# youuuuuuh.net
KiCad netlist of a schematic drawn in EAGLE
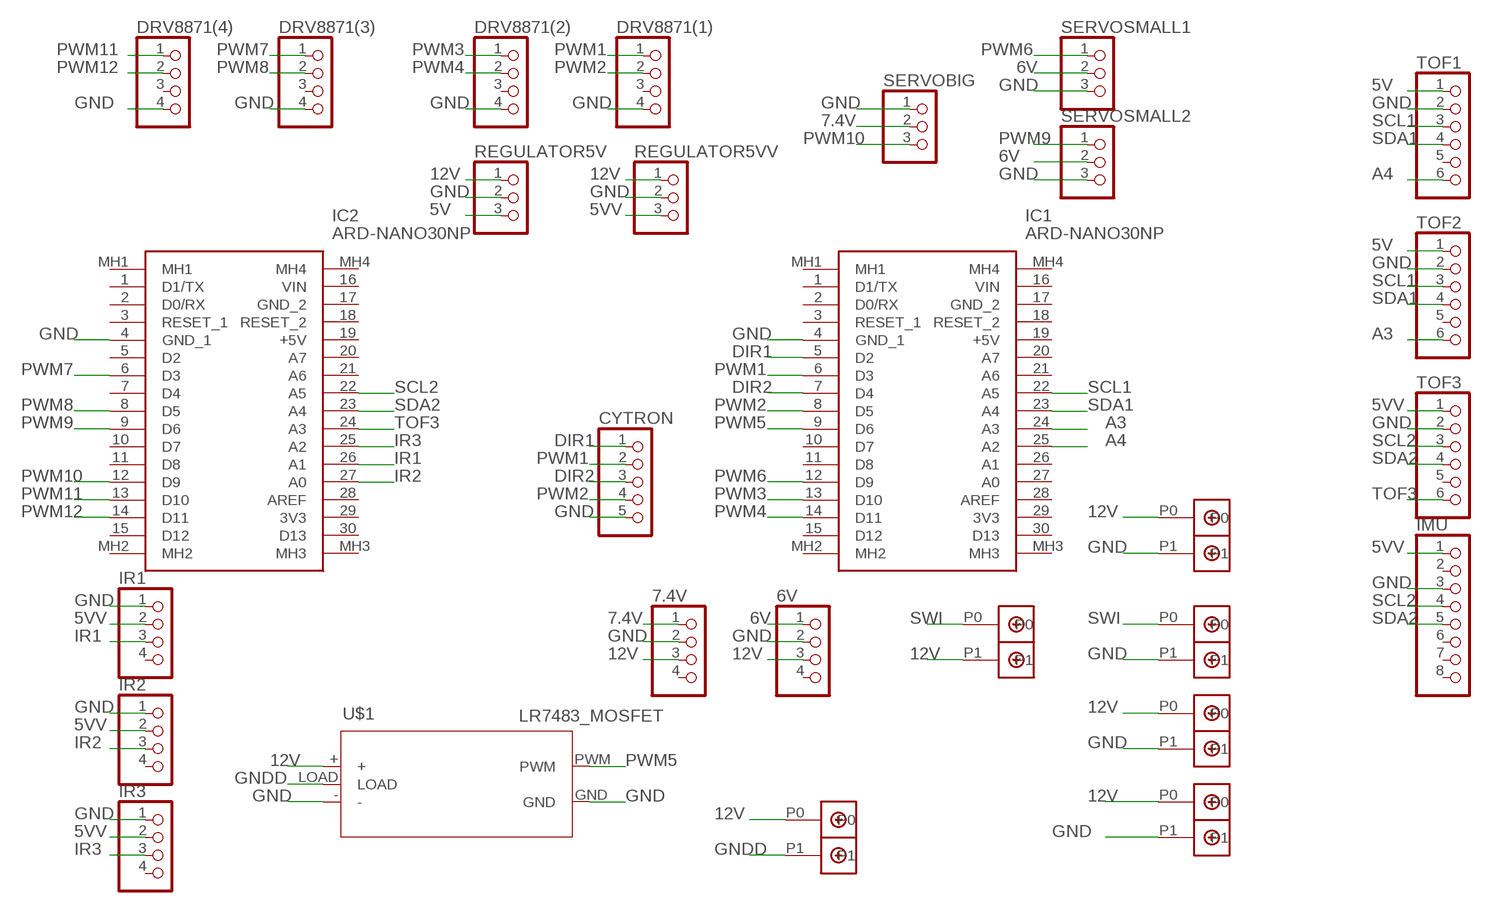
[diagram p0: schematic, sheet 1]

(export (version "E")
  (design (tool "Eeschema 10.0.6"))
  (components
    (comp (ref "6V")
      (value "PINHD-1X4")
      (footprint "eagle-import:1X04")
      (libsource (lib "eagle-import") (part "pinhead_325_PINHD-1X4"))
    )
    (comp (ref "7.4V")
      (value "PINHD-1X4")
      (footprint "eagle-import:1X04")
      (libsource (lib "eagle-import") (part "pinhead_325_PINHD-1X4"))
    )
    (comp (ref "BATERY")
      (value "DBCONN-1X2")
      (footprint "eagle-import:DBCONN-1X2")
      (libsource (lib "eagle-import") (part "DBCONN-1X2"))
    )
    (comp (ref "BUCKSERVO")
      (value "DBCONN-1X2")
      (footprint "eagle-import:DBCONN-1X2")
      (libsource (lib "eagle-import") (part "DBCONN-1X2"))
    )
    (comp (ref "CYTRON")
      (value "PINHD-1X5")
      (footprint "eagle-import:1X05")
      (libsource (lib "eagle-import") (part "PINHD-1X5"))
    )
    (comp (ref "CYTRONPOWER")
      (value "DBCONN-1X2")
      (footprint "eagle-import:DBCONN-1X2")
      (libsource (lib "eagle-import") (part "DBCONN-1X2"))
    )
    (comp (ref "DRV8871(1)")
      (value "PINHD-1X4")
      (footprint "eagle-import:1X04")
      (libsource (lib "eagle-import") (part "pinhead_325_PINHD-1X4"))
    )
    (comp (ref "DRV8871(2)")
      (value "PINHD-1X4")
      (footprint "eagle-import:1X04")
      (libsource (lib "eagle-import") (part "pinhead_325_PINHD-1X4"))
    )
    (comp (ref "DRV8871(3)")
      (value "PINHD-1X4")
      (footprint "eagle-import:1X04")
      (libsource (lib "eagle-import") (part "pinhead_325_PINHD-1X4"))
    )
    (comp (ref "DRV8871(4)")
      (value "PINHD-1X4")
      (footprint "eagle-import:1X04")
      (libsource (lib "eagle-import") (part "pinhead_325_PINHD-1X4"))
    )
    (comp (ref "IC1")
      (value "ARD-NANO30NP")
      (footprint "eagle-import:ARDNANO30NP")
      (fields (field (name "MOUSER_PART_NUMBER") "992-ARD-NANO30NP"))
      (libsource (lib "eagle-import") (part "ARD-NANO30NP"))
    )
    (comp (ref "IC2")
      (value "ARD-NANO30NP")
      (footprint "eagle-import:ARDNANO30NP")
      (fields (field (name "MOUSER_PART_NUMBER") "992-ARD-NANO30NP"))
      (libsource (lib "eagle-import") (part "ARD-NANO30NP"))
    )
    (comp (ref "IMU")
      (value "PINHD-1X8")
      (footprint "eagle-import:1X08")
      (libsource (lib "eagle-import") (part "PINHD-1X8"))
    )
    (comp (ref "IR1")
      (value "PINHD-1X4")
      (footprint "eagle-import:1X04")
      (libsource (lib "eagle-import") (part "PINHD-1X4"))
    )
    (comp (ref "IR2")
      (value "PINHD-1X4")
      (footprint "eagle-import:1X04")
      (libsource (lib "eagle-import") (part "PINHD-1X4"))
    )
    (comp (ref "IR3")
      (value "PINHD-1X4")
      (footprint "eagle-import:1X04")
      (libsource (lib "eagle-import") (part "PINHD-1X4"))
    )
    (comp (ref "LEDS1")
      (value "DBCONN-1X2")
      (footprint "eagle-import:DBCONN-1X2")
      (libsource (lib "eagle-import") (part "DBCONN-1X2"))
    )
    (comp (ref "LEDS2")
      (value "DBCONN-1X2")
      (footprint "eagle-import:DBCONN-1X2")
      (libsource (lib "eagle-import") (part "DBCONN-1X2"))
    )
    (comp (ref "LEDS3")
      (value "DBCONN-1X2")
      (footprint "eagle-import:DBCONN-1X2")
      (libsource (lib "eagle-import") (part "DBCONN-1X2"))
    )
    (comp (ref "REGULATOR5V")
      (value "PINHD-1X3")
      (footprint "eagle-import:1X03")
      (libsource (lib "eagle-import") (part "pinhead_325_PINHD-1X3"))
    )
    (comp (ref "REGULATOR5VV")
      (value "PINHD-1X3")
      (footprint "eagle-import:1X03")
      (libsource (lib "eagle-import") (part "PINHD-1X3"))
    )
    (comp (ref "SERVOBIG")
      (value "PINHD-1X3")
      (footprint "eagle-import:1X03")
      (libsource (lib "eagle-import") (part "pinhead_325_PINHD-1X3"))
    )
    (comp (ref "SERVOSMALL1")
      (value "PINHD-1X3")
      (footprint "eagle-import:1X03")
      (libsource (lib "eagle-import") (part "pinhead_325_PINHD-1X3"))
    )
    (comp (ref "SERVOSMALL2")
      (value "PINHD-1X3")
      (footprint "eagle-import:1X03")
      (libsource (lib "eagle-import") (part "pinhead_325_PINHD-1X3"))
    )
    (comp (ref "TOF1")
      (value "PINHD-1X6")
      (footprint "eagle-import:1X06")
      (libsource (lib "eagle-import") (part "PINHD-1X6"))
    )
    (comp (ref "TOF2")
      (value "PINHD-1X6")
      (footprint "eagle-import:1X06")
      (libsource (lib "eagle-import") (part "PINHD-1X6"))
    )
    (comp (ref "TOF3")
      (value "PINHD-1X6")
      (footprint "eagle-import:1X06")
      (libsource (lib "eagle-import") (part "PINHD-1X6"))
    )
    (comp (ref "U$1")
      (value "LR7483_MOSFET")
      (footprint "eagle-import:LR7483_MOSFET")
      (libsource (lib "eagle-import") (part "LR7483_MOSFET"))
    )
  )
  (nets
    (net (code "1") (name "/5V") (class "Default")
      (node (ref "REGULATOR5V") (pin "3") (pinfunction "3_3") (pintype "passive"))
      (node (ref "TOF1") (pin "1") (pinfunction "1_1") (pintype "passive"))
      (node (ref "TOF2") (pin "1") (pinfunction "1_1") (pintype "passive"))
    )
    (net (code "2") (name "/5VV") (class "Default")
      (node (ref "IMU") (pin "1") (pinfunction "1_1") (pintype "passive"))
      (node (ref "IR1") (pin "2") (pinfunction "2_2") (pintype "passive"))
      (node (ref "IR2") (pin "2") (pinfunction "2_2") (pintype "passive"))
      (node (ref "IR3") (pin "2") (pinfunction "2_2") (pintype "passive"))
      (node (ref "REGULATOR5VV") (pin "3") (pinfunction "3_3") (pintype "passive"))
      (node (ref "TOF3") (pin "1") (pinfunction "1_1") (pintype "passive"))
    )
    (net (code "3") (name "/6V") (class "Default")
      (node (ref "6V") (pin "1") (pinfunction "1_1") (pintype "passive"))
      (node (ref "SERVOSMALL1") (pin "2") (pinfunction "2_2") (pintype "passive"))
      (node (ref "SERVOSMALL2") (pin "2") (pinfunction "2_2") (pintype "passive"))
    )
    (net (code "4") (name "/7.4V") (class "Default")
      (node (ref "7.4V") (pin "1") (pinfunction "1_1") (pintype "passive"))
      (node (ref "SERVOBIG") (pin "2") (pinfunction "2_2") (pintype "passive"))
    )
    (net (code "5") (name "/12V") (class "Default")
      (node (ref "6V") (pin "3") (pinfunction "3_3") (pintype "passive"))
      (node (ref "7.4V") (pin "3") (pinfunction "3_3") (pintype "passive"))
      (node (ref "BUCKSERVO") (pin "P0") (pinfunction "P0_P0") (pintype "bidirectional"))
      (node (ref "CYTRONPOWER") (pin "P0") (pinfunction "P0_P0") (pintype "bidirectional"))
      (node (ref "LEDS1") (pin "P1") (pinfunction "P1_P1") (pintype "bidirectional"))
      (node (ref "LEDS2") (pin "P0") (pinfunction "P0_P0") (pintype "bidirectional"))
      (node (ref "LEDS3") (pin "P0") (pinfunction "P0_P0") (pintype "bidirectional"))
      (node (ref "REGULATOR5V") (pin "1") (pinfunction "1_1") (pintype "passive"))
      (node (ref "REGULATOR5VV") (pin "1") (pinfunction "1_1") (pintype "passive"))
      (node (ref "U$1") (pin "+") (pinfunction "+_+") (pintype "bidirectional"))
    )
    (net (code "6") (name "/A3") (class "Default")
      (node (ref "IC1") (pin "24") (pinfunction "A3_24") (pintype "bidirectional"))
      (node (ref "TOF2") (pin "6") (pinfunction "6_6") (pintype "passive"))
    )
    (net (code "7") (name "/A4") (class "Default")
      (node (ref "IC1") (pin "25") (pinfunction "A2_25") (pintype "bidirectional"))
      (node (ref "TOF1") (pin "6") (pinfunction "6_6") (pintype "passive"))
    )
    (net (code "8") (name "/DIR1") (class "Default")
      (node (ref "CYTRON") (pin "1") (pinfunction "1_1") (pintype "passive"))
      (node (ref "IC1") (pin "5") (pinfunction "D2_5") (pintype "bidirectional"))
    )
    (net (code "9") (name "/DIR2") (class "Default")
      (node (ref "CYTRON") (pin "3") (pinfunction "3_3") (pintype "passive"))
      (node (ref "IC1") (pin "7") (pinfunction "D4_7") (pintype "bidirectional"))
    )
    (net (code "10") (name "/GND") (class "Default")
      (node (ref "6V") (pin "2") (pinfunction "2_2") (pintype "passive"))
      (node (ref "7.4V") (pin "2") (pinfunction "2_2") (pintype "passive"))
      (node (ref "BATERY") (pin "P1") (pinfunction "P1_P1") (pintype "bidirectional"))
      (node (ref "BUCKSERVO") (pin "P1") (pinfunction "P1_P1") (pintype "bidirectional"))
      (node (ref "CYTRON") (pin "5") (pinfunction "5_5") (pintype "passive"))
      (node (ref "CYTRONPOWER") (pin "P1") (pinfunction "P1_P1") (pintype "bidirectional"))
      (node (ref "DRV8871(1)") (pin "4") (pinfunction "4_4") (pintype "passive"))
      (node (ref "DRV8871(2)") (pin "4") (pinfunction "4_4") (pintype "passive"))
      (node (ref "DRV8871(3)") (pin "4") (pinfunction "4_4") (pintype "passive"))
      (node (ref "DRV8871(4)") (pin "4") (pinfunction "4_4") (pintype "passive"))
      (node (ref "IC1") (pin "4") (pinfunction "GND_1_4") (pintype "bidirectional"))
      (node (ref "IC2") (pin "4") (pinfunction "GND_1_4") (pintype "bidirectional"))
      (node (ref "IMU") (pin "3") (pinfunction "3_3") (pintype "passive"))
      (node (ref "IR1") (pin "1") (pinfunction "1_1") (pintype "passive"))
      (node (ref "IR2") (pin "1") (pinfunction "1_1") (pintype "passive"))
      (node (ref "IR3") (pin "1") (pinfunction "1_1") (pintype "passive"))
      (node (ref "LEDS2") (pin "P1") (pinfunction "P1_P1") (pintype "bidirectional"))
      (node (ref "REGULATOR5V") (pin "2") (pinfunction "2_2") (pintype "passive"))
      (node (ref "REGULATOR5VV") (pin "2") (pinfunction "2_2") (pintype "passive"))
      (node (ref "SERVOBIG") (pin "1") (pinfunction "1_1") (pintype "passive"))
      (node (ref "SERVOSMALL1") (pin "3") (pinfunction "3_3") (pintype "passive"))
      (node (ref "SERVOSMALL2") (pin "3") (pinfunction "3_3") (pintype "passive"))
      (node (ref "TOF1") (pin "2") (pinfunction "2_2") (pintype "passive"))
      (node (ref "TOF2") (pin "2") (pinfunction "2_2") (pintype "passive"))
      (node (ref "TOF3") (pin "2") (pinfunction "2_2") (pintype "passive"))
      (node (ref "U$1") (pin "-") (pinfunction "-_-") (pintype "bidirectional"))
      (node (ref "U$1") (pin "GND") (pinfunction "GND_GND") (pintype "bidirectional"))
    )
    (net (code "11") (name "/GNDD") (class "Default")
      (node (ref "LEDS3") (pin "P1") (pinfunction "P1_P1") (pintype "bidirectional"))
      (node (ref "U$1") (pin "LOAD") (pinfunction "LOAD_LOAD") (pintype "bidirectional"))
    )
    (net (code "12") (name "/IR1") (class "Default")
      (node (ref "IC2") (pin "26") (pinfunction "A1_26") (pintype "bidirectional"))
      (node (ref "IR1") (pin "3") (pinfunction "3_3") (pintype "passive"))
    )
    (net (code "13") (name "/IR2") (class "Default")
      (node (ref "IC2") (pin "27") (pinfunction "A0_27") (pintype "bidirectional"))
      (node (ref "IR2") (pin "3") (pinfunction "3_3") (pintype "passive"))
    )
    (net (code "14") (name "/IR3") (class "Default")
      (node (ref "IC2") (pin "25") (pinfunction "A2_25") (pintype "bidirectional"))
      (node (ref "IR3") (pin "3") (pinfunction "3_3") (pintype "passive"))
    )
    (net (code "15") (name "/PWM1") (class "Default")
      (node (ref "CYTRON") (pin "2") (pinfunction "2_2") (pintype "passive"))
      (node (ref "DRV8871(1)") (pin "1") (pinfunction "1_1") (pintype "passive"))
      (node (ref "IC1") (pin "6") (pinfunction "D3_6") (pintype "bidirectional"))
    )
    (net (code "16") (name "/PWM2") (class "Default")
      (node (ref "CYTRON") (pin "4") (pinfunction "4_4") (pintype "passive"))
      (node (ref "DRV8871(1)") (pin "2") (pinfunction "2_2") (pintype "passive"))
      (node (ref "IC1") (pin "8") (pinfunction "D5_8") (pintype "bidirectional"))
    )
    (net (code "17") (name "/PWM3") (class "Default")
      (node (ref "DRV8871(2)") (pin "1") (pinfunction "1_1") (pintype "passive"))
      (node (ref "IC1") (pin "13") (pinfunction "D10_13") (pintype "bidirectional"))
    )
    (net (code "18") (name "/PWM4") (class "Default")
      (node (ref "DRV8871(2)") (pin "2") (pinfunction "2_2") (pintype "passive"))
      (node (ref "IC1") (pin "14") (pinfunction "D11_14") (pintype "bidirectional"))
    )
    (net (code "19") (name "/PWM5") (class "Default")
      (node (ref "IC1") (pin "9") (pinfunction "D6_9") (pintype "bidirectional"))
      (node (ref "U$1") (pin "PWM") (pinfunction "PWM_PWM") (pintype "bidirectional"))
    )
    (net (code "20") (name "/PWM6") (class "Default")
      (node (ref "IC1") (pin "12") (pinfunction "D9_12") (pintype "bidirectional"))
      (node (ref "SERVOSMALL1") (pin "1") (pinfunction "1_1") (pintype "passive"))
    )
    (net (code "21") (name "/PWM7") (class "Default")
      (node (ref "DRV8871(3)") (pin "1") (pinfunction "1_1") (pintype "passive"))
      (node (ref "IC2") (pin "6") (pinfunction "D3_6") (pintype "bidirectional"))
    )
    (net (code "22") (name "/PWM8") (class "Default")
      (node (ref "DRV8871(3)") (pin "2") (pinfunction "2_2") (pintype "passive"))
      (node (ref "IC2") (pin "8") (pinfunction "D5_8") (pintype "bidirectional"))
    )
    (net (code "23") (name "/PWM9") (class "Default")
      (node (ref "IC2") (pin "9") (pinfunction "D6_9") (pintype "bidirectional"))
      (node (ref "SERVOSMALL2") (pin "1") (pinfunction "1_1") (pintype "passive"))
    )
    (net (code "24") (name "/PWM10") (class "Default")
      (node (ref "IC2") (pin "12") (pinfunction "D9_12") (pintype "bidirectional"))
      (node (ref "SERVOBIG") (pin "3") (pinfunction "3_3") (pintype "passive"))
    )
    (net (code "25") (name "/PWM11") (class "Default")
      (node (ref "DRV8871(4)") (pin "1") (pinfunction "1_1") (pintype "passive"))
      (node (ref "IC2") (pin "13") (pinfunction "D10_13") (pintype "bidirectional"))
    )
    (net (code "26") (name "/PWM12") (class "Default")
      (node (ref "DRV8871(4)") (pin "2") (pinfunction "2_2") (pintype "passive"))
      (node (ref "IC2") (pin "14") (pinfunction "D11_14") (pintype "bidirectional"))
    )
    (net (code "27") (name "/SCL1") (class "Default")
      (node (ref "IC1") (pin "22") (pinfunction "A5_22") (pintype "bidirectional"))
      (node (ref "TOF1") (pin "3") (pinfunction "3_3") (pintype "passive"))
      (node (ref "TOF2") (pin "3") (pinfunction "3_3") (pintype "passive"))
    )
    (net (code "28") (name "/SCL2") (class "Default")
      (node (ref "IC2") (pin "22") (pinfunction "A5_22") (pintype "bidirectional"))
      (node (ref "IMU") (pin "4") (pinfunction "4_4") (pintype "passive"))
      (node (ref "TOF3") (pin "3") (pinfunction "3_3") (pintype "passive"))
    )
    (net (code "29") (name "/SDA1") (class "Default")
      (node (ref "IC1") (pin "23") (pinfunction "A4_23") (pintype "bidirectional"))
      (node (ref "TOF1") (pin "4") (pinfunction "4_4") (pintype "passive"))
      (node (ref "TOF2") (pin "4") (pinfunction "4_4") (pintype "passive"))
    )
    (net (code "30") (name "/SDA2") (class "Default")
      (node (ref "IC2") (pin "23") (pinfunction "A4_23") (pintype "bidirectional"))
      (node (ref "IMU") (pin "5") (pinfunction "5_5") (pintype "passive"))
      (node (ref "TOF3") (pin "4") (pinfunction "4_4") (pintype "passive"))
    )
    (net (code "31") (name "/SWI") (class "Default")
      (node (ref "BATERY") (pin "P0") (pinfunction "P0_P0") (pintype "bidirectional"))
      (node (ref "LEDS1") (pin "P0") (pinfunction "P0_P0") (pintype "bidirectional"))
    )
    (net (code "32") (name "/TOF3") (class "Default")
      (node (ref "IC2") (pin "24") (pinfunction "A3_24") (pintype "bidirectional"))
      (node (ref "TOF3") (pin "6") (pinfunction "6_6") (pintype "passive"))
    )
    (net (code "33") (name "unconnected-(6V-Pad4)") (class "Default")
      (node (ref "6V") (pin "4") (pinfunction "4_4") (pintype "passive"))
    )
    (net (code "34") (name "unconnected-(7.4V-Pad4)") (class "Default")
      (node (ref "7.4V") (pin "4") (pinfunction "4_4") (pintype "passive"))
    )
    (net (code "35") (name "unconnected-(DRV8871(1)-Pad3)") (class "Default")
      (node (ref "DRV8871(1)") (pin "3") (pinfunction "3_3") (pintype "passive"))
    )
    (net (code "36") (name "unconnected-(DRV8871(2)-Pad3)") (class "Default")
      (node (ref "DRV8871(2)") (pin "3") (pinfunction "3_3") (pintype "passive"))
    )
    (net (code "37") (name "unconnected-(DRV8871(3)-Pad3)") (class "Default")
      (node (ref "DRV8871(3)") (pin "3") (pinfunction "3_3") (pintype "passive"))
    )
    (net (code "38") (name "unconnected-(DRV8871(4)-Pad3)") (class "Default")
      (node (ref "DRV8871(4)") (pin "3") (pinfunction "3_3") (pintype "passive"))
    )
    (net (code "39") (name "unconnected-(IC1-+5V-Pad19)") (class "Default")
      (node (ref "IC1") (pin "19") (pinfunction "+5V_19") (pintype "bidirectional"))
    )
    (net (code "40") (name "unconnected-(IC1-3V3-Pad29)") (class "Default")
      (node (ref "IC1") (pin "29") (pinfunction "3V3_29") (pintype "bidirectional"))
    )
    (net (code "41") (name "unconnected-(IC1-A0-Pad27)") (class "Default")
      (node (ref "IC1") (pin "27") (pinfunction "A0_27") (pintype "bidirectional"))
    )
    (net (code "42") (name "unconnected-(IC1-A1-Pad26)") (class "Default")
      (node (ref "IC1") (pin "26") (pinfunction "A1_26") (pintype "bidirectional"))
    )
    (net (code "43") (name "unconnected-(IC1-A6-Pad21)") (class "Default")
      (node (ref "IC1") (pin "21") (pinfunction "A6_21") (pintype "bidirectional"))
    )
    (net (code "44") (name "unconnected-(IC1-A7-Pad20)") (class "Default")
      (node (ref "IC1") (pin "20") (pinfunction "A7_20") (pintype "bidirectional"))
    )
    (net (code "45") (name "unconnected-(IC1-AREF-Pad28)") (class "Default")
      (node (ref "IC1") (pin "28") (pinfunction "AREF_28") (pintype "bidirectional"))
    )
    (net (code "46") (name "unconnected-(IC1-D0{slash}RX-Pad2)") (class "Default")
      (node (ref "IC1") (pin "2") (pinfunction "D0/RX_2") (pintype "bidirectional"))
    )
    (net (code "47") (name "unconnected-(IC1-D1{slash}TX-Pad1)") (class "Default")
      (node (ref "IC1") (pin "1") (pinfunction "D1/TX_1") (pintype "bidirectional"))
    )
    (net (code "48") (name "unconnected-(IC1-D7-Pad10)") (class "Default")
      (node (ref "IC1") (pin "10") (pinfunction "D7_10") (pintype "bidirectional"))
    )
    (net (code "49") (name "unconnected-(IC1-D8-Pad11)") (class "Default")
      (node (ref "IC1") (pin "11") (pinfunction "D8_11") (pintype "bidirectional"))
    )
    (net (code "50") (name "unconnected-(IC1-D12-Pad15)") (class "Default")
      (node (ref "IC1") (pin "15") (pinfunction "D12_15") (pintype "bidirectional"))
    )
    (net (code "51") (name "unconnected-(IC1-D13-Pad30)") (class "Default")
      (node (ref "IC1") (pin "30") (pinfunction "D13_30") (pintype "bidirectional"))
    )
    (net (code "52") (name "unconnected-(IC1-GND_2-Pad17)") (class "Default")
      (node (ref "IC1") (pin "17") (pinfunction "GND_2_17") (pintype "bidirectional"))
    )
    (net (code "53") (name "unconnected-(IC1-PadMH1)") (class "Default")
      (node (ref "IC1") (pin "MH1") (pinfunction "MH1_MH1") (pintype "bidirectional"))
    )
    (net (code "54") (name "unconnected-(IC1-PadMH2)") (class "Default")
      (node (ref "IC1") (pin "MH2") (pinfunction "MH2_MH2") (pintype "bidirectional"))
    )
    (net (code "55") (name "unconnected-(IC1-PadMH3)") (class "Default")
      (node (ref "IC1") (pin "MH3") (pinfunction "MH3_MH3") (pintype "bidirectional"))
    )
    (net (code "56") (name "unconnected-(IC1-PadMH4)") (class "Default")
      (node (ref "IC1") (pin "MH4") (pinfunction "MH4_MH4") (pintype "bidirectional"))
    )
    (net (code "57") (name "unconnected-(IC1-RESET_1-Pad3)") (class "Default")
      (node (ref "IC1") (pin "3") (pinfunction "RESET_1_3") (pintype "bidirectional"))
    )
    (net (code "58") (name "unconnected-(IC1-RESET_2-Pad18)") (class "Default")
      (node (ref "IC1") (pin "18") (pinfunction "RESET_2_18") (pintype "bidirectional"))
    )
    (net (code "59") (name "unconnected-(IC1-VIN-Pad16)") (class "Default")
      (node (ref "IC1") (pin "16") (pinfunction "VIN_16") (pintype "bidirectional"))
    )
    (net (code "60") (name "unconnected-(IC2-+5V-Pad19)") (class "Default")
      (node (ref "IC2") (pin "19") (pinfunction "+5V_19") (pintype "bidirectional"))
    )
    (net (code "61") (name "unconnected-(IC2-3V3-Pad29)") (class "Default")
      (node (ref "IC2") (pin "29") (pinfunction "3V3_29") (pintype "bidirectional"))
    )
    (net (code "62") (name "unconnected-(IC2-A6-Pad21)") (class "Default")
      (node (ref "IC2") (pin "21") (pinfunction "A6_21") (pintype "bidirectional"))
    )
    (net (code "63") (name "unconnected-(IC2-A7-Pad20)") (class "Default")
      (node (ref "IC2") (pin "20") (pinfunction "A7_20") (pintype "bidirectional"))
    )
    (net (code "64") (name "unconnected-(IC2-AREF-Pad28)") (class "Default")
      (node (ref "IC2") (pin "28") (pinfunction "AREF_28") (pintype "bidirectional"))
    )
    (net (code "65") (name "unconnected-(IC2-D0{slash}RX-Pad2)") (class "Default")
      (node (ref "IC2") (pin "2") (pinfunction "D0/RX_2") (pintype "bidirectional"))
    )
    (net (code "66") (name "unconnected-(IC2-D1{slash}TX-Pad1)") (class "Default")
      (node (ref "IC2") (pin "1") (pinfunction "D1/TX_1") (pintype "bidirectional"))
    )
    (net (code "67") (name "unconnected-(IC2-D2-Pad5)") (class "Default")
      (node (ref "IC2") (pin "5") (pinfunction "D2_5") (pintype "bidirectional"))
    )
    (net (code "68") (name "unconnected-(IC2-D4-Pad7)") (class "Default")
      (node (ref "IC2") (pin "7") (pinfunction "D4_7") (pintype "bidirectional"))
    )
    (net (code "69") (name "unconnected-(IC2-D7-Pad10)") (class "Default")
      (node (ref "IC2") (pin "10") (pinfunction "D7_10") (pintype "bidirectional"))
    )
    (net (code "70") (name "unconnected-(IC2-D8-Pad11)") (class "Default")
      (node (ref "IC2") (pin "11") (pinfunction "D8_11") (pintype "bidirectional"))
    )
    (net (code "71") (name "unconnected-(IC2-D12-Pad15)") (class "Default")
      (node (ref "IC2") (pin "15") (pinfunction "D12_15") (pintype "bidirectional"))
    )
    (net (code "72") (name "unconnected-(IC2-D13-Pad30)") (class "Default")
      (node (ref "IC2") (pin "30") (pinfunction "D13_30") (pintype "bidirectional"))
    )
    (net (code "73") (name "unconnected-(IC2-GND_2-Pad17)") (class "Default")
      (node (ref "IC2") (pin "17") (pinfunction "GND_2_17") (pintype "bidirectional"))
    )
    (net (code "74") (name "unconnected-(IC2-PadMH1)") (class "Default")
      (node (ref "IC2") (pin "MH1") (pinfunction "MH1_MH1") (pintype "bidirectional"))
    )
    (net (code "75") (name "unconnected-(IC2-PadMH2)") (class "Default")
      (node (ref "IC2") (pin "MH2") (pinfunction "MH2_MH2") (pintype "bidirectional"))
    )
    (net (code "76") (name "unconnected-(IC2-PadMH3)") (class "Default")
      (node (ref "IC2") (pin "MH3") (pinfunction "MH3_MH3") (pintype "bidirectional"))
    )
    (net (code "77") (name "unconnected-(IC2-PadMH4)") (class "Default")
      (node (ref "IC2") (pin "MH4") (pinfunction "MH4_MH4") (pintype "bidirectional"))
    )
    (net (code "78") (name "unconnected-(IC2-RESET_1-Pad3)") (class "Default")
      (node (ref "IC2") (pin "3") (pinfunction "RESET_1_3") (pintype "bidirectional"))
    )
    (net (code "79") (name "unconnected-(IC2-RESET_2-Pad18)") (class "Default")
      (node (ref "IC2") (pin "18") (pinfunction "RESET_2_18") (pintype "bidirectional"))
    )
    (net (code "80") (name "unconnected-(IC2-VIN-Pad16)") (class "Default")
      (node (ref "IC2") (pin "16") (pinfunction "VIN_16") (pintype "bidirectional"))
    )
    (net (code "81") (name "unconnected-(IMU-Pad2)") (class "Default")
      (node (ref "IMU") (pin "2") (pinfunction "2_2") (pintype "passive"))
    )
    (net (code "82") (name "unconnected-(IMU-Pad6)") (class "Default")
      (node (ref "IMU") (pin "6") (pinfunction "6_6") (pintype "passive"))
    )
    (net (code "83") (name "unconnected-(IMU-Pad7)") (class "Default")
      (node (ref "IMU") (pin "7") (pinfunction "7_7") (pintype "passive"))
    )
    (net (code "84") (name "unconnected-(IMU-Pad8)") (class "Default")
      (node (ref "IMU") (pin "8") (pinfunction "8_8") (pintype "passive"))
    )
    (net (code "85") (name "unconnected-(IR1-Pad4)") (class "Default")
      (node (ref "IR1") (pin "4") (pinfunction "4_4") (pintype "passive"))
    )
    (net (code "86") (name "unconnected-(IR2-Pad4)") (class "Default")
      (node (ref "IR2") (pin "4") (pinfunction "4_4") (pintype "passive"))
    )
    (net (code "87") (name "unconnected-(IR3-Pad4)") (class "Default")
      (node (ref "IR3") (pin "4") (pinfunction "4_4") (pintype "passive"))
    )
    (net (code "88") (name "unconnected-(TOF1-Pad5)") (class "Default")
      (node (ref "TOF1") (pin "5") (pinfunction "5_5") (pintype "passive"))
    )
    (net (code "89") (name "unconnected-(TOF2-Pad5)") (class "Default")
      (node (ref "TOF2") (pin "5") (pinfunction "5_5") (pintype "passive"))
    )
    (net (code "90") (name "unconnected-(TOF3-Pad5)") (class "Default")
      (node (ref "TOF3") (pin "5") (pinfunction "5_5") (pintype "passive"))
    )
  )
)
